# EspIC.net
KiCad netlist of a schematic drawn in Altium Designer
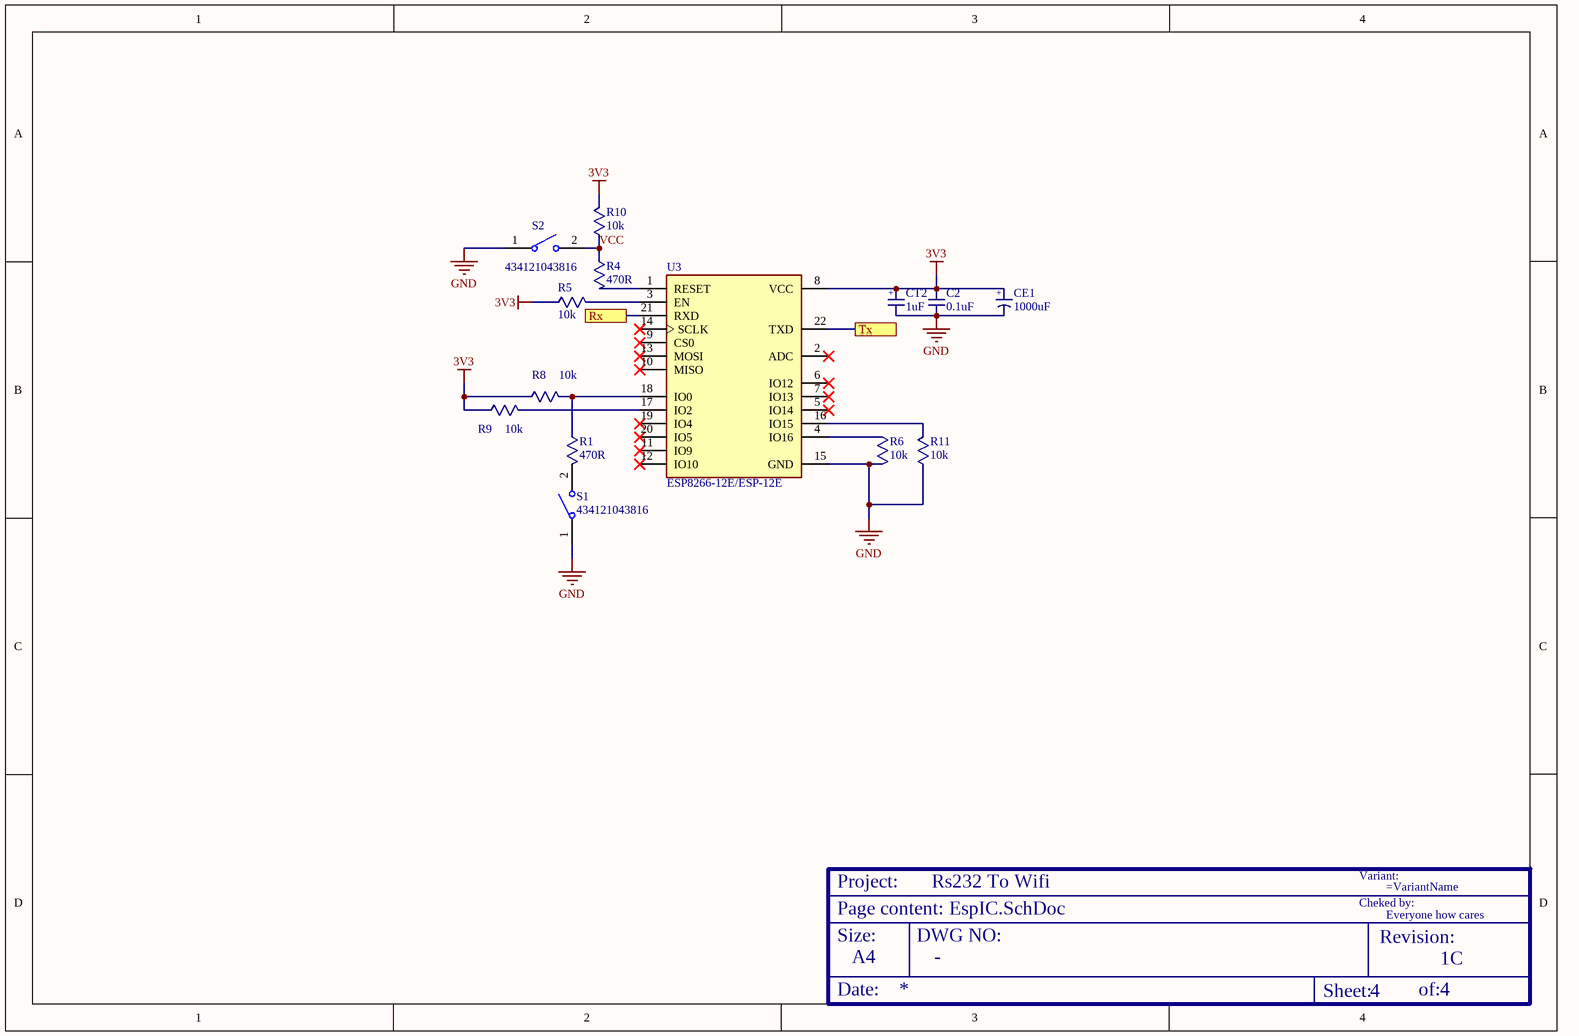
[diagram p0: EspIC.SchDoc]

(export (version "E")
  (design (tool "Eeschema 10.0.6"))
  (components
    (comp (ref "C2")
      (value "0.1uF")
      (footprint "0603C")
      (description "Ceramic Capacitor")
      (libsource (lib "General_Libs") (part "CC"))
    )
    (comp (ref "CE1")
      (value "1000uF")
      (footprint "WCAP-AS5H_8x10.5")
      (description "Eletrolitic Capacitor")
      (libsource (lib "General_Libs") (part "CE"))
    )
    (comp (ref "CT2")
      (value "1uF")
      (footprint "0603T")
      (description "Condensador Tantalum")
      (fields (field (name "Comment") "Tantalum capacitor"))
      (libsource (lib "General_Libs") (part "CT"))
    )
    (comp (ref "R1")
      (value "470R")
      (footprint "0603")
      (description "Res")
      (libsource (lib "General_Libs") (part "Res"))
    )
    (comp (ref "R4")
      (value "470R")
      (footprint "0603")
      (description "Res")
      (libsource (lib "General_Libs") (part "Res"))
    )
    (comp (ref "R5")
      (value "10k")
      (footprint "0603")
      (description "Res")
      (libsource (lib "General_Libs") (part "Res"))
    )
    (comp (ref "R6")
      (value "10k")
      (footprint "0603")
      (description "Res")
      (libsource (lib "General_Libs") (part "Res"))
    )
    (comp (ref "R8")
      (value "10k")
      (footprint "0603")
      (description "Res")
      (libsource (lib "General_Libs") (part "Res"))
    )
    (comp (ref "R9")
      (value "10k")
      (footprint "0603")
      (description "Res")
      (libsource (lib "General_Libs") (part "Res"))
    )
    (comp (ref "R10")
      (value "10k")
      (footprint "0603")
      (description "Res")
      (libsource (lib "General_Libs") (part "Res"))
    )
    (comp (ref "R11")
      (value "10k")
      (footprint "0603")
      (description "Res")
      (libsource (lib "General_Libs") (part "Res"))
    )
    (comp (ref "S1")
      (value "434121043816")
      (footprint "434121043816")
      (description "6x3.5mm SMD WS-TASV, height 4.3 mm, 160 gf")
      (fields (field (name "Comment") "Swich"))
      (libsource (lib "General_Libs") (part "switch 2 patas smd"))
    )
    (comp (ref "S2")
      (value "434121043816")
      (footprint "434121043816")
      (description "6x3.5mm SMD WS-TASV, height 4.3 mm, 160 gf")
      (fields (field (name "Comment") "Swich"))
      (libsource (lib "General_Libs") (part "switch 2 patas smd"))
    )
    (comp (ref "U3")
      (value "ESP8266-12E/ESP-12E")
      (footprint "XCVR_ESP8266-12E/ESP-12E")
      (fields (field (name "MF") "AI-Thinker"))
      (libsource (lib "General_Libs") (part "ESP8266-12E/ESP-12E"))
    )
  )
  (nets
    (net (code "1") (name "/Rx") (class "Default")
      (node (ref "U3") (pin "21") (pinfunction "RXD_21") (pintype "passive"))
    )
    (net (code "2") (name "/Tx") (class "Default")
      (node (ref "U3") (pin "22") (pinfunction "TXD_22") (pintype "passive"))
    )
    (net (code "3") (name "/VCC") (class "Default")
      (node (ref "R10") (pin "1") (pinfunction "1_1") (pintype "passive"))
      (node (ref "R4") (pin "1") (pinfunction "1_1") (pintype "passive"))
      (node (ref "S2") (pin "2") (pinfunction "2_2") (pintype "passive"))
    )
    (net (code "4") (name "3V3") (class "Default")
      (node (ref "C2") (pin "1") (pinfunction "1_1") (pintype "passive"))
      (node (ref "CE1") (pin "1") (pinfunction "1_1") (pintype "passive"))
      (node (ref "CT2") (pin "1") (pinfunction "1_1") (pintype "passive"))
      (node (ref "R10") (pin "2") (pinfunction "2_2") (pintype "passive"))
      (node (ref "R5") (pin "1") (pinfunction "1_1") (pintype "passive"))
      (node (ref "R8") (pin "1") (pinfunction "1_1") (pintype "passive"))
      (node (ref "R9") (pin "1") (pinfunction "1_1") (pintype "passive"))
      (node (ref "U3") (pin "8") (pinfunction "VCC_8") (pintype "passive"))
    )
    (net (code "5") (name "GND") (class "Default")
      (node (ref "C2") (pin "2") (pinfunction "2_2") (pintype "passive"))
      (node (ref "CE1") (pin "2") (pinfunction "2_2") (pintype "passive"))
      (node (ref "CT2") (pin "2") (pinfunction "2_2") (pintype "passive"))
      (node (ref "R11") (pin "1") (pinfunction "1_1") (pintype "passive"))
      (node (ref "R6") (pin "2") (pinfunction "2_2") (pintype "passive"))
      (node (ref "S1") (pin "1") (pinfunction "1_1") (pintype "passive"))
      (node (ref "S2") (pin "1") (pinfunction "1_1") (pintype "passive"))
      (node (ref "U3") (pin "15") (pinfunction "GND_15") (pintype "passive"))
    )
    (net (code "6") (name "Net-(R1-Pad2)") (class "Default")
      (node (ref "R1") (pin "2") (pinfunction "2_2") (pintype "passive"))
      (node (ref "S1") (pin "2") (pinfunction "2_2") (pintype "passive"))
    )
    (net (code "7") (name "Net-(U3-EN)") (class "Default")
      (node (ref "R5") (pin "2") (pinfunction "2_2") (pintype "passive"))
      (node (ref "U3") (pin "3") (pinfunction "EN_3") (pintype "passive"))
    )
    (net (code "8") (name "Net-(U3-IO0)") (class "Default")
      (node (ref "R1") (pin "1") (pinfunction "1_1") (pintype "passive"))
      (node (ref "R8") (pin "2") (pinfunction "2_2") (pintype "passive"))
      (node (ref "U3") (pin "18") (pinfunction "IO0_18") (pintype "passive"))
    )
    (net (code "9") (name "Net-(U3-IO2)") (class "Default")
      (node (ref "R9") (pin "2") (pinfunction "2_2") (pintype "passive"))
      (node (ref "U3") (pin "17") (pinfunction "IO2_17") (pintype "passive"))
    )
    (net (code "10") (name "Net-(U3-IO15)") (class "Default")
      (node (ref "R11") (pin "2") (pinfunction "2_2") (pintype "passive"))
      (node (ref "U3") (pin "16") (pinfunction "IO15_16") (pintype "passive"))
    )
    (net (code "11") (name "Net-(U3-IO16)") (class "Default")
      (node (ref "R6") (pin "1") (pinfunction "1_1") (pintype "passive"))
      (node (ref "U3") (pin "4") (pinfunction "IO16_4") (pintype "passive"))
    )
    (net (code "12") (name "Net-(U3-RESET)") (class "Default")
      (node (ref "R4") (pin "2") (pinfunction "2_2") (pintype "passive"))
      (node (ref "U3") (pin "1") (pinfunction "RESET_1") (pintype "passive"))
    )
    (net (code "13") (name "unconnected-(U3-ADC-Pad2)") (class "Default")
      (node (ref "U3") (pin "2") (pinfunction "ADC_2") (pintype "passive+no_connect"))
    )
    (net (code "14") (name "unconnected-(U3-CS0-Pad9)") (class "Default")
      (node (ref "U3") (pin "9") (pinfunction "CS0_9") (pintype "passive+no_connect"))
    )
    (net (code "15") (name "unconnected-(U3-IO4-Pad19)") (class "Default")
      (node (ref "U3") (pin "19") (pinfunction "IO4_19") (pintype "passive+no_connect"))
    )
    (net (code "16") (name "unconnected-(U3-IO5-Pad20)") (class "Default")
      (node (ref "U3") (pin "20") (pinfunction "IO5_20") (pintype "passive+no_connect"))
    )
    (net (code "17") (name "unconnected-(U3-IO9-Pad11)") (class "Default")
      (node (ref "U3") (pin "11") (pinfunction "IO9_11") (pintype "passive+no_connect"))
    )
    (net (code "18") (name "unconnected-(U3-IO10-Pad12)") (class "Default")
      (node (ref "U3") (pin "12") (pinfunction "IO10_12") (pintype "passive+no_connect"))
    )
    (net (code "19") (name "unconnected-(U3-IO12-Pad6)") (class "Default")
      (node (ref "U3") (pin "6") (pinfunction "IO12_6") (pintype "passive+no_connect"))
    )
    (net (code "20") (name "unconnected-(U3-IO13-Pad7)") (class "Default")
      (node (ref "U3") (pin "7") (pinfunction "IO13_7") (pintype "passive+no_connect"))
    )
    (net (code "21") (name "unconnected-(U3-IO14-Pad5)") (class "Default")
      (node (ref "U3") (pin "5") (pinfunction "IO14_5") (pintype "passive+no_connect"))
    )
    (net (code "22") (name "unconnected-(U3-MISO-Pad10)") (class "Default")
      (node (ref "U3") (pin "10") (pinfunction "MISO_10") (pintype "passive+no_connect"))
    )
    (net (code "23") (name "unconnected-(U3-MOSI-Pad13)") (class "Default")
      (node (ref "U3") (pin "13") (pinfunction "MOSI_13") (pintype "passive+no_connect"))
    )
    (net (code "24") (name "unconnected-(U3-SCLK-Pad14)") (class "Default")
      (node (ref "U3") (pin "14") (pinfunction "SCLK_14") (pintype "passive+no_connect"))
    )
  )
)
